# connector_schematic.net
KiCad netlist of a schematic drawn in EAGLE
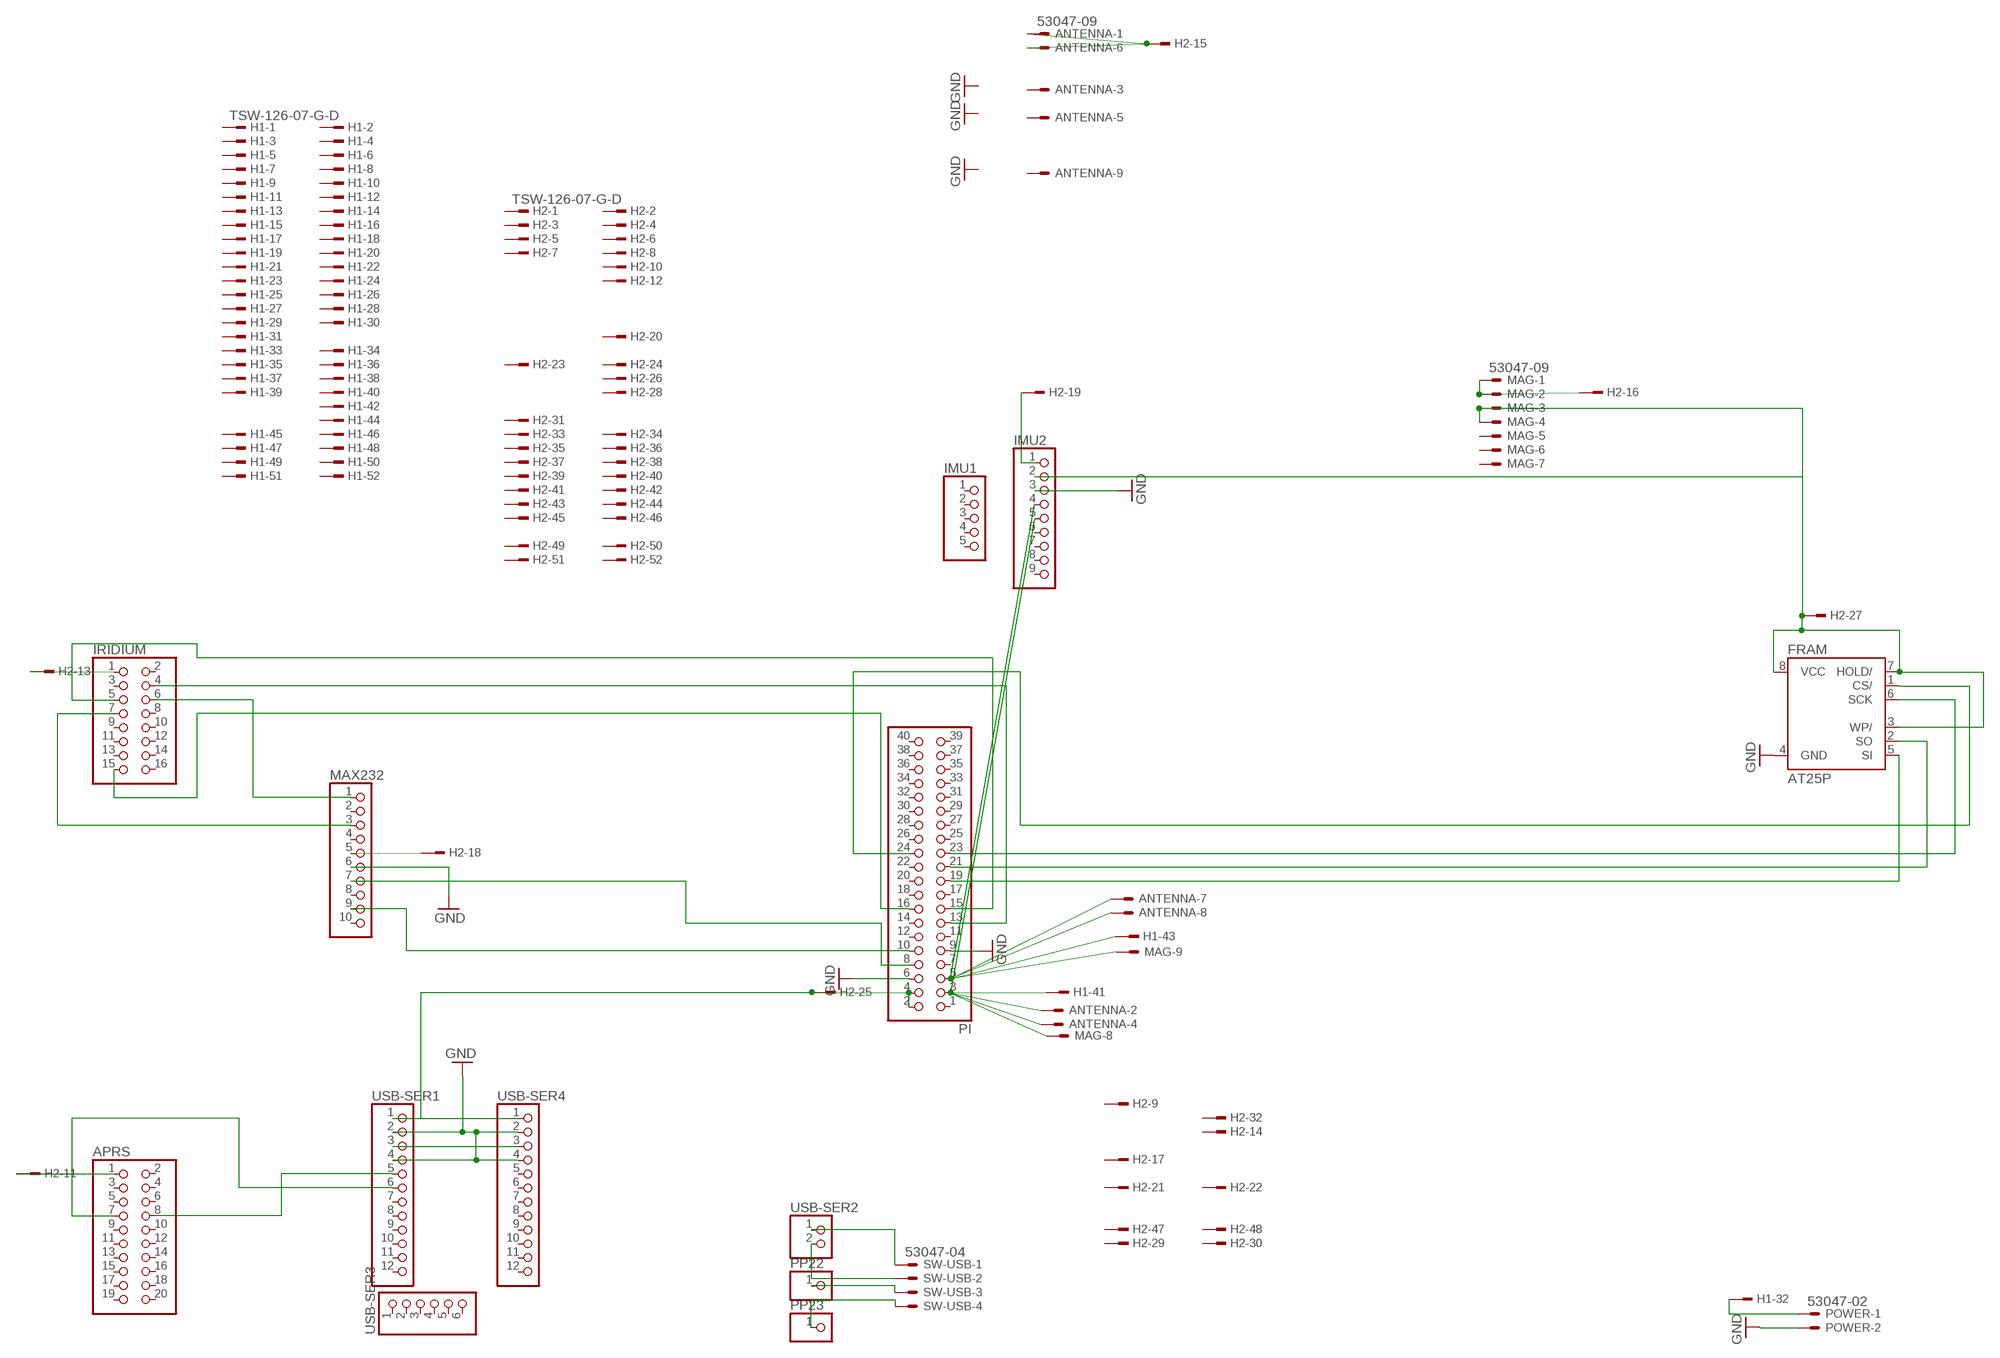
[diagram p0: schematic, sheet 1]

(export (version "E")
  (design (tool "Eeschema 10.0.6"))
  (components
    (comp (ref "ANTENNA")
      (value "53047-09")
      (footprint "eagle-import:53047-09")
      (fields (field (name "MF") "MOLEX") (field (name "MPN") "53047-0910"))
      (libsource (lib "eagle-import") (part "53?-09047"))
    )
    (comp (ref "APRS")
      (value "PINHD-2X10")
      (footprint "eagle-import:2X10")
      (libsource (lib "eagle-import") (part "PINHD-2X10"))
    )
    (comp (ref "FRAM")
      (value "AT25P")
      (footprint "eagle-import:DIL08")
      (fields (field (name "MPN") "CAT25040LI-G"))
      (libsource (lib "eagle-import") (part "AT25P"))
    )
    (comp (ref "H1")
      (value "TSW-126-07-G-D")
      (footprint "eagle-import:TSW-126-XX-G-D")
      (fields (field (name "MF") "Samtec Inc."))
      (libsource (lib "eagle-import") (part "TSW-126--G-D07"))
    )
    (comp (ref "H2")
      (value "TSW-126-07-G-D")
      (footprint "eagle-import:TSW-126-XX-G-D")
      (fields (field (name "MF") "Samtec Inc."))
      (libsource (lib "eagle-import") (part "TSW-126--G-D07"))
    )
    (comp (ref "IMU1")
      (value "PINHD-1X5")
      (footprint "eagle-import:1X05")
      (libsource (lib "eagle-import") (part "PINHD-1X5"))
    )
    (comp (ref "IMU2")
      (value "PINHD-1X9")
      (footprint "eagle-import:1X09")
      (libsource (lib "eagle-import") (part "PINHD-1X9"))
    )
    (comp (ref "IRIDIUM")
      (value "PINHD-2X8")
      (footprint "eagle-import:2X08")
      (libsource (lib "eagle-import") (part "PINHD-2X8"))
    )
    (comp (ref "MAG")
      (value "53047-09")
      (footprint "eagle-import:53047-09")
      (fields (field (name "MF") "MOLEX") (field (name "MPN") "53047-0910"))
      (libsource (lib "eagle-import") (part "53?-09047"))
    )
    (comp (ref "MAX232")
      (value "PINHD-1X10")
      (footprint "eagle-import:1X10")
      (libsource (lib "eagle-import") (part "PINHD-1X10"))
    )
    (comp (ref "PI")
      (value "PINHD-2X20")
      (footprint "eagle-import:2X20")
      (libsource (lib "eagle-import") (part "PINHD-2X20"))
    )
    (comp (ref "POWER")
      (value "53047-02")
      (footprint "eagle-import:53047-02")
      (fields (field (name "MF") "MOLEX") (field (name "MPN") "53047-0210"))
      (libsource (lib "eagle-import") (part "53?-02047"))
    )
    (comp (ref "PP22")
      (value "PINHD-1X1")
      (footprint "eagle-import:1X01")
      (libsource (lib "eagle-import") (part "PINHD-1X1"))
    )
    (comp (ref "PP23")
      (value "PINHD-1X1")
      (footprint "eagle-import:1X01")
      (libsource (lib "eagle-import") (part "PINHD-1X1"))
    )
    (comp (ref "SW-USB")
      (value "53047-04")
      (footprint "eagle-import:53047-04")
      (fields (field (name "MF") "WALDOM/MOLEX") (field (name "MPN") "53047-0410"))
      (libsource (lib "eagle-import") (part "53?-04047"))
    )
    (comp (ref "USB-SER1")
      (value "PINHD-1X12")
      (footprint "eagle-import:1X12")
      (libsource (lib "eagle-import") (part "PINHD-1X12"))
    )
    (comp (ref "USB-SER2")
      (value "PINHD-1X2")
      (footprint "eagle-import:1X02")
      (libsource (lib "eagle-import") (part "PINHD-1X2"))
    )
    (comp (ref "USB-SER3")
      (value "PINHD-1X6")
      (footprint "eagle-import:1X06")
      (libsource (lib "eagle-import") (part "PINHD-1X6"))
    )
    (comp (ref "USB-SER4")
      (value "PINHD-1X12")
      (footprint "eagle-import:1X12")
      (libsource (lib "eagle-import") (part "PINHD-1X12"))
    )
  )
  (nets
    (net (code "1") (name "GND") (class "Default")
      (node (ref "FRAM") (pin "4") (pinfunction "GND_4") (pintype "power_in"))
      (node (ref "IMU2") (pin "3") (pinfunction "3_3") (pintype "passive"))
      (node (ref "MAX232") (pin "6") (pinfunction "6_6") (pintype "passive"))
      (node (ref "PI") (pin "6") (pinfunction "6_6") (pintype "passive"))
      (node (ref "PI") (pin "9") (pinfunction "9_9") (pintype "passive"))
      (node (ref "POWER") (pin "2") (pinfunction "S_2") (pintype "passive"))
      (node (ref "USB-SER1") (pin "2") (pinfunction "2_2") (pintype "passive"))
      (node (ref "USB-SER1") (pin "4") (pinfunction "4_4") (pintype "passive"))
      (node (ref "USB-SER4") (pin "2") (pinfunction "2_2") (pintype "passive"))
      (node (ref "USB-SER4") (pin "4") (pinfunction "4_4") (pintype "passive"))
    )
    (net (code "2") (name "Net-(ANTENNAA-S)") (class "Default")
      (node (ref "ANTENNA") (pin "1") (pinfunction "S_1") (pintype "passive"))
      (node (ref "ANTENNA") (pin "6") (pinfunction "S_6") (pintype "passive"))
      (node (ref "H2") (pin "15") (pinfunction "1_15") (pintype "passive"))
    )
    (net (code "3") (name "Net-(ANTENNAB-S)") (class "Default")
      (node (ref "ANTENNA") (pin "2") (pinfunction "S_2") (pintype "passive"))
      (node (ref "ANTENNA") (pin "4") (pinfunction "S_4") (pintype "passive"))
      (node (ref "H1") (pin "41") (pinfunction "1_41") (pintype "passive"))
      (node (ref "IMU2") (pin "5") (pinfunction "5_5") (pintype "passive"))
      (node (ref "MAG") (pin "8") (pinfunction "S_8") (pintype "passive"))
      (node (ref "PI") (pin "3") (pinfunction "3_3") (pintype "passive"))
    )
    (net (code "4") (name "Net-(ANTENNAG-S)") (class "Default")
      (node (ref "ANTENNA") (pin "7") (pinfunction "S_7") (pintype "passive"))
      (node (ref "ANTENNA") (pin "8") (pinfunction "S_8") (pintype "passive"))
      (node (ref "H1") (pin "43") (pinfunction "1_43") (pintype "passive"))
      (node (ref "IMU2") (pin "4") (pinfunction "4_4") (pintype "passive"))
      (node (ref "MAG") (pin "9") (pinfunction "S_9") (pintype "passive"))
      (node (ref "PI") (pin "5") (pinfunction "5_5") (pintype "passive"))
    )
    (net (code "5") (name "Net-(APRS-Pad7)") (class "Default")
      (node (ref "APRS") (pin "7") (pinfunction "7_7") (pintype "passive"))
      (node (ref "USB-SER1") (pin "6") (pinfunction "6_6") (pintype "passive"))
    )
    (net (code "6") (name "Net-(APRS-Pad8)") (class "Default")
      (node (ref "APRS") (pin "8") (pinfunction "8_8") (pintype "passive"))
      (node (ref "USB-SER1") (pin "5") (pinfunction "5_5") (pintype "passive"))
    )
    (net (code "7") (name "Net-(FRAM-CS{slash})") (class "Default")
      (node (ref "FRAM") (pin "1") (pinfunction "CS/_1") (pintype "input"))
      (node (ref "PI") (pin "24") (pinfunction "24_24") (pintype "passive"))
    )
    (net (code "8") (name "Net-(FRAM-HOLD{slash})") (class "Default")
      (node (ref "FRAM") (pin "3") (pinfunction "WP/_3") (pintype "input"))
      (node (ref "FRAM") (pin "7") (pinfunction "HOLD/_7") (pintype "input"))
      (node (ref "FRAM") (pin "8") (pinfunction "VCC_8") (pintype "power_in"))
      (node (ref "H2") (pin "27") (pinfunction "1_27") (pintype "passive"))
      (node (ref "IMU2") (pin "2") (pinfunction "2_2") (pintype "passive"))
      (node (ref "MAG") (pin "3") (pinfunction "S_3") (pintype "passive"))
      (node (ref "MAG") (pin "4") (pinfunction "S_4") (pintype "passive"))
    )
    (net (code "9") (name "Net-(FRAM-SCK)") (class "Default")
      (node (ref "FRAM") (pin "6") (pinfunction "SCK_6") (pintype "bidirectional"))
      (node (ref "PI") (pin "23") (pinfunction "23_23") (pintype "passive"))
    )
    (net (code "10") (name "Net-(FRAM-SI)") (class "Default")
      (node (ref "FRAM") (pin "5") (pinfunction "SI_5") (pintype "bidirectional"))
      (node (ref "PI") (pin "19") (pinfunction "19_19") (pintype "passive"))
    )
    (net (code "11") (name "Net-(FRAM-SO)") (class "Default")
      (node (ref "FRAM") (pin "2") (pinfunction "SO_2") (pintype "input"))
      (node (ref "PI") (pin "21") (pinfunction "21_21") (pintype "passive"))
    )
    (net (code "12") (name "Net-(H1Z-1)") (class "Default")
      (node (ref "H1") (pin "32") (pinfunction "1_32") (pintype "passive"))
      (node (ref "POWER") (pin "1") (pinfunction "S_1") (pintype "passive"))
    )
    (net (code "13") (name "Net-(H2C-1)") (class "Default")
      (node (ref "APRS") (pin "1") (pinfunction "1_1") (pintype "passive"))
      (node (ref "H2") (pin "11") (pinfunction "1_11") (pintype "passive"))
    )
    (net (code "14") (name "Net-(H2E-1)") (class "Default")
      (node (ref "H2") (pin "13") (pinfunction "1_13") (pintype "passive"))
      (node (ref "IRIDIUM") (pin "1") (pinfunction "1_1") (pintype "passive"))
    )
    (net (code "15") (name "Net-(H2H-1)") (class "Default")
      (node (ref "H2") (pin "16") (pinfunction "1_16") (pintype "passive"))
      (node (ref "MAG") (pin "1") (pinfunction "S_1") (pintype "passive"))
      (node (ref "MAG") (pin "2") (pinfunction "S_2") (pintype "passive"))
    )
    (net (code "16") (name "Net-(H2J-1)") (class "Default")
      (node (ref "H2") (pin "18") (pinfunction "1_18") (pintype "passive"))
      (node (ref "MAX232") (pin "5") (pinfunction "5_5") (pintype "passive"))
    )
    (net (code "17") (name "Net-(H2K-1)") (class "Default")
      (node (ref "H2") (pin "19") (pinfunction "1_19") (pintype "passive"))
      (node (ref "IMU2") (pin "1") (pinfunction "1_1") (pintype "passive"))
    )
    (net (code "18") (name "Net-(H2R-1)") (class "Default")
      (node (ref "H2") (pin "25") (pinfunction "1_25") (pintype "passive"))
      (node (ref "PI") (pin "2") (pinfunction "2_2") (pintype "passive"))
      (node (ref "PI") (pin "4") (pinfunction "4_4") (pintype "passive"))
      (node (ref "USB-SER1") (pin "1") (pinfunction "1_1") (pintype "passive"))
      (node (ref "USB-SER4") (pin "1") (pinfunction "1_1") (pintype "passive"))
    )
    (net (code "19") (name "Net-(IRIDIUM-Pad4)") (class "Default")
      (node (ref "IRIDIUM") (pin "4") (pinfunction "4_4") (pintype "passive"))
      (node (ref "PI") (pin "13") (pinfunction "13_13") (pintype "passive"))
    )
    (net (code "20") (name "Net-(IRIDIUM-Pad5)") (class "Default")
      (node (ref "IRIDIUM") (pin "5") (pinfunction "5_5") (pintype "passive"))
      (node (ref "PI") (pin "15") (pinfunction "15_15") (pintype "passive"))
    )
    (net (code "21") (name "Net-(IRIDIUM-Pad6)") (class "Default")
      (node (ref "IRIDIUM") (pin "6") (pinfunction "6_6") (pintype "passive"))
      (node (ref "MAX232") (pin "1") (pinfunction "1_1") (pintype "passive"))
    )
    (net (code "22") (name "Net-(IRIDIUM-Pad7)") (class "Default")
      (node (ref "IRIDIUM") (pin "7") (pinfunction "7_7") (pintype "passive"))
      (node (ref "MAX232") (pin "3") (pinfunction "3_3") (pintype "passive"))
    )
    (net (code "23") (name "Net-(IRIDIUM-Pad15)") (class "Default")
      (node (ref "IRIDIUM") (pin "15") (pinfunction "15_15") (pintype "passive"))
      (node (ref "PI") (pin "16") (pinfunction "16_16") (pintype "passive"))
    )
    (net (code "24") (name "Net-(MAX232-Pad7)") (class "Default")
      (node (ref "MAX232") (pin "7") (pinfunction "7_7") (pintype "passive"))
      (node (ref "PI") (pin "8") (pinfunction "8_8") (pintype "passive"))
    )
    (net (code "25") (name "Net-(MAX232-Pad9)") (class "Default")
      (node (ref "MAX232") (pin "9") (pinfunction "9_9") (pintype "passive"))
      (node (ref "PI") (pin "10") (pinfunction "10_10") (pintype "passive"))
    )
    (net (code "26") (name "Net-(SW-USBB-S)") (class "Default")
      (node (ref "SW-USB") (pin "2") (pinfunction "S_2") (pintype "passive"))
      (node (ref "USB-SER2") (pin "2") (pinfunction "2_2") (pintype "passive"))
    )
    (net (code "27") (name "Net-(SW-USBC-S)") (class "Default")
      (node (ref "PP22") (pin "1") (pinfunction "1_1") (pintype "passive"))
      (node (ref "SW-USB") (pin "3") (pinfunction "S_3") (pintype "passive"))
    )
    (net (code "28") (name "Net-(SW-USBD-S)") (class "Default")
      (node (ref "PP23") (pin "1") (pinfunction "1_1") (pintype "passive"))
      (node (ref "SW-USB") (pin "4") (pinfunction "S_4") (pintype "passive"))
    )
    (net (code "29") (name "Net-(USB-SER1-Pad3)") (class "Default")
      (node (ref "USB-SER1") (pin "3") (pinfunction "3_3") (pintype "passive"))
      (node (ref "USB-SER4") (pin "3") (pinfunction "3_3") (pintype "passive"))
    )
    (net (code "30") (name "unconnected-(ANTENNAC-S-Pad3)") (class "Default")
      (node (ref "ANTENNA") (pin "3") (pinfunction "S_3") (pintype "passive"))
    )
    (net (code "31") (name "unconnected-(ANTENNAE-S-Pad5)") (class "Default")
      (node (ref "ANTENNA") (pin "5") (pinfunction "S_5") (pintype "passive"))
    )
    (net (code "32") (name "unconnected-(ANTENNAI-S-Pad9)") (class "Default")
      (node (ref "ANTENNA") (pin "9") (pinfunction "S_9") (pintype "passive"))
    )
    (net (code "33") (name "unconnected-(APRS-Pad2)") (class "Default")
      (node (ref "APRS") (pin "2") (pinfunction "2_2") (pintype "passive"))
    )
    (net (code "34") (name "unconnected-(APRS-Pad3)") (class "Default")
      (node (ref "APRS") (pin "3") (pinfunction "3_3") (pintype "passive"))
    )
    (net (code "35") (name "unconnected-(APRS-Pad4)") (class "Default")
      (node (ref "APRS") (pin "4") (pinfunction "4_4") (pintype "passive"))
    )
    (net (code "36") (name "unconnected-(APRS-Pad5)") (class "Default")
      (node (ref "APRS") (pin "5") (pinfunction "5_5") (pintype "passive"))
    )
    (net (code "37") (name "unconnected-(APRS-Pad6)") (class "Default")
      (node (ref "APRS") (pin "6") (pinfunction "6_6") (pintype "passive"))
    )
    (net (code "38") (name "unconnected-(APRS-Pad9)") (class "Default")
      (node (ref "APRS") (pin "9") (pinfunction "9_9") (pintype "passive"))
    )
    (net (code "39") (name "unconnected-(APRS-Pad10)") (class "Default")
      (node (ref "APRS") (pin "10") (pinfunction "10_10") (pintype "passive"))
    )
    (net (code "40") (name "unconnected-(APRS-Pad11)") (class "Default")
      (node (ref "APRS") (pin "11") (pinfunction "11_11") (pintype "passive"))
    )
    (net (code "41") (name "unconnected-(APRS-Pad12)") (class "Default")
      (node (ref "APRS") (pin "12") (pinfunction "12_12") (pintype "passive"))
    )
    (net (code "42") (name "unconnected-(APRS-Pad13)") (class "Default")
      (node (ref "APRS") (pin "13") (pinfunction "13_13") (pintype "passive"))
    )
    (net (code "43") (name "unconnected-(APRS-Pad14)") (class "Default")
      (node (ref "APRS") (pin "14") (pinfunction "14_14") (pintype "passive"))
    )
    (net (code "44") (name "unconnected-(APRS-Pad15)") (class "Default")
      (node (ref "APRS") (pin "15") (pinfunction "15_15") (pintype "passive"))
    )
    (net (code "45") (name "unconnected-(APRS-Pad16)") (class "Default")
      (node (ref "APRS") (pin "16") (pinfunction "16_16") (pintype "passive"))
    )
    (net (code "46") (name "unconnected-(APRS-Pad17)") (class "Default")
      (node (ref "APRS") (pin "17") (pinfunction "17_17") (pintype "passive"))
    )
    (net (code "47") (name "unconnected-(APRS-Pad18)") (class "Default")
      (node (ref "APRS") (pin "18") (pinfunction "18_18") (pintype "passive"))
    )
    (net (code "48") (name "unconnected-(APRS-Pad19)") (class "Default")
      (node (ref "APRS") (pin "19") (pinfunction "19_19") (pintype "passive"))
    )
    (net (code "49") (name "unconnected-(APRS-Pad20)") (class "Default")
      (node (ref "APRS") (pin "20") (pinfunction "20_20") (pintype "passive"))
    )
    (net (code "50") (name "unconnected-(H1-Pad1)") (class "Default")
      (node (ref "H1") (pin "1") (pinfunction "1_1") (pintype "passive"))
    )
    (net (code "51") (name "unconnected-(H1AA-1-Pad33)") (class "Default")
      (node (ref "H1") (pin "33") (pinfunction "1_33") (pintype "passive"))
    )
    (net (code "52") (name "unconnected-(H1AB-1-Pad34)") (class "Default")
      (node (ref "H1") (pin "34") (pinfunction "1_34") (pintype "passive"))
    )
    (net (code "53") (name "unconnected-(H1AC-1-Pad35)") (class "Default")
      (node (ref "H1") (pin "35") (pinfunction "1_35") (pintype "passive"))
    )
    (net (code "54") (name "unconnected-(H1AD-1-Pad36)") (class "Default")
      (node (ref "H1") (pin "36") (pinfunction "1_36") (pintype "passive"))
    )
    (net (code "55") (name "unconnected-(H1AE-1-Pad37)") (class "Default")
      (node (ref "H1") (pin "37") (pinfunction "1_37") (pintype "passive"))
    )
    (net (code "56") (name "unconnected-(H1AF-1-Pad38)") (class "Default")
      (node (ref "H1") (pin "38") (pinfunction "1_38") (pintype "passive"))
    )
    (net (code "57") (name "unconnected-(H1AG-1-Pad39)") (class "Default")
      (node (ref "H1") (pin "39") (pinfunction "1_39") (pintype "passive"))
    )
    (net (code "58") (name "unconnected-(H1AH-1-Pad4)") (class "Default")
      (node (ref "H1") (pin "4") (pinfunction "1_4") (pintype "passive"))
    )
    (net (code "59") (name "unconnected-(H1AI-1-Pad40)") (class "Default")
      (node (ref "H1") (pin "40") (pinfunction "1_40") (pintype "passive"))
    )
    (net (code "60") (name "unconnected-(H1AK-1-Pad42)") (class "Default")
      (node (ref "H1") (pin "42") (pinfunction "1_42") (pintype "passive"))
    )
    (net (code "61") (name "unconnected-(H1AM-1-Pad44)") (class "Default")
      (node (ref "H1") (pin "44") (pinfunction "1_44") (pintype "passive"))
    )
    (net (code "62") (name "unconnected-(H1AN-1-Pad45)") (class "Default")
      (node (ref "H1") (pin "45") (pinfunction "1_45") (pintype "passive"))
    )
    (net (code "63") (name "unconnected-(H1AO-1-Pad46)") (class "Default")
      (node (ref "H1") (pin "46") (pinfunction "1_46") (pintype "passive"))
    )
    (net (code "64") (name "unconnected-(H1AP-1-Pad47)") (class "Default")
      (node (ref "H1") (pin "47") (pinfunction "1_47") (pintype "passive"))
    )
    (net (code "65") (name "unconnected-(H1AQ-1-Pad48)") (class "Default")
      (node (ref "H1") (pin "48") (pinfunction "1_48") (pintype "passive"))
    )
    (net (code "66") (name "unconnected-(H1AR-1-Pad49)") (class "Default")
      (node (ref "H1") (pin "49") (pinfunction "1_49") (pintype "passive"))
    )
    (net (code "67") (name "unconnected-(H1AS-1-Pad5)") (class "Default")
      (node (ref "H1") (pin "5") (pinfunction "1_5") (pintype "passive"))
    )
    (net (code "68") (name "unconnected-(H1AT-1-Pad50)") (class "Default")
      (node (ref "H1") (pin "50") (pinfunction "1_50") (pintype "passive"))
    )
    (net (code "69") (name "unconnected-(H1AU-1-Pad51)") (class "Default")
      (node (ref "H1") (pin "51") (pinfunction "1_51") (pintype "passive"))
    )
    (net (code "70") (name "unconnected-(H1AV-1-Pad52)") (class "Default")
      (node (ref "H1") (pin "52") (pinfunction "1_52") (pintype "passive"))
    )
    (net (code "71") (name "unconnected-(H1AW-1-Pad6)") (class "Default")
      (node (ref "H1") (pin "6") (pinfunction "1_6") (pintype "passive"))
    )
    (net (code "72") (name "unconnected-(H1AX-1-Pad7)") (class "Default")
      (node (ref "H1") (pin "7") (pinfunction "1_7") (pintype "passive"))
    )
    (net (code "73") (name "unconnected-(H1AY-1-Pad8)") (class "Default")
      (node (ref "H1") (pin "8") (pinfunction "1_8") (pintype "passive"))
    )
    (net (code "74") (name "unconnected-(H1AZ-1-Pad9)") (class "Default")
      (node (ref "H1") (pin "9") (pinfunction "1_9") (pintype "passive"))
    )
    (net (code "75") (name "unconnected-(H1B-1-Pad10)") (class "Default")
      (node (ref "H1") (pin "10") (pinfunction "1_10") (pintype "passive"))
    )
    (net (code "76") (name "unconnected-(H1C-1-Pad11)") (class "Default")
      (node (ref "H1") (pin "11") (pinfunction "1_11") (pintype "passive"))
    )
    (net (code "77") (name "unconnected-(H1D-1-Pad12)") (class "Default")
      (node (ref "H1") (pin "12") (pinfunction "1_12") (pintype "passive"))
    )
    (net (code "78") (name "unconnected-(H1E-1-Pad13)") (class "Default")
      (node (ref "H1") (pin "13") (pinfunction "1_13") (pintype "passive"))
    )
    (net (code "79") (name "unconnected-(H1F-1-Pad14)") (class "Default")
      (node (ref "H1") (pin "14") (pinfunction "1_14") (pintype "passive"))
    )
    (net (code "80") (name "unconnected-(H1G-1-Pad15)") (class "Default")
      (node (ref "H1") (pin "15") (pinfunction "1_15") (pintype "passive"))
    )
    (net (code "81") (name "unconnected-(H1H-1-Pad16)") (class "Default")
      (node (ref "H1") (pin "16") (pinfunction "1_16") (pintype "passive"))
    )
    (net (code "82") (name "unconnected-(H1I-1-Pad17)") (class "Default")
      (node (ref "H1") (pin "17") (pinfunction "1_17") (pintype "passive"))
    )
    (net (code "83") (name "unconnected-(H1J-1-Pad18)") (class "Default")
      (node (ref "H1") (pin "18") (pinfunction "1_18") (pintype "passive"))
    )
    (net (code "84") (name "unconnected-(H1K-1-Pad19)") (class "Default")
      (node (ref "H1") (pin "19") (pinfunction "1_19") (pintype "passive"))
    )
    (net (code "85") (name "unconnected-(H1L-1-Pad2)") (class "Default")
      (node (ref "H1") (pin "2") (pinfunction "1_2") (pintype "passive"))
    )
    (net (code "86") (name "unconnected-(H1M-1-Pad20)") (class "Default")
      (node (ref "H1") (pin "20") (pinfunction "1_20") (pintype "passive"))
    )
    (net (code "87") (name "unconnected-(H1N-1-Pad21)") (class "Default")
      (node (ref "H1") (pin "21") (pinfunction "1_21") (pintype "passive"))
    )
    (net (code "88") (name "unconnected-(H1O-1-Pad22)") (class "Default")
      (node (ref "H1") (pin "22") (pinfunction "1_22") (pintype "passive"))
    )
    (net (code "89") (name "unconnected-(H1P-1-Pad23)") (class "Default")
      (node (ref "H1") (pin "23") (pinfunction "1_23") (pintype "passive"))
    )
    (net (code "90") (name "unconnected-(H1Q-1-Pad24)") (class "Default")
      (node (ref "H1") (pin "24") (pinfunction "1_24") (pintype "passive"))
    )
    (net (code "91") (name "unconnected-(H1R-1-Pad25)") (class "Default")
      (node (ref "H1") (pin "25") (pinfunction "1_25") (pintype "passive"))
    )
    (net (code "92") (name "unconnected-(H1S-1-Pad26)") (class "Default")
      (node (ref "H1") (pin "26") (pinfunction "1_26") (pintype "passive"))
    )
    (net (code "93") (name "unconnected-(H1T-1-Pad27)") (class "Default")
      (node (ref "H1") (pin "27") (pinfunction "1_27") (pintype "passive"))
    )
    (net (code "94") (name "unconnected-(H1U-1-Pad28)") (class "Default")
      (node (ref "H1") (pin "28") (pinfunction "1_28") (pintype "passive"))
    )
    (net (code "95") (name "unconnected-(H1V-1-Pad29)") (class "Default")
      (node (ref "H1") (pin "29") (pinfunction "1_29") (pintype "passive"))
    )
    (net (code "96") (name "unconnected-(H1W-1-Pad3)") (class "Default")
      (node (ref "H1") (pin "3") (pinfunction "1_3") (pintype "passive"))
    )
    (net (code "97") (name "unconnected-(H1X-1-Pad30)") (class "Default")
      (node (ref "H1") (pin "30") (pinfunction "1_30") (pintype "passive"))
    )
    (net (code "98") (name "unconnected-(H1Y-1-Pad31)") (class "Default")
      (node (ref "H1") (pin "31") (pinfunction "1_31") (pintype "passive"))
    )
    (net (code "99") (name "unconnected-(H2-Pad1)") (class "Default")
      (node (ref "H2") (pin "1") (pinfunction "1_1") (pintype "passive"))
    )
    (net (code "100") (name "unconnected-(H2AA-1-Pad33)") (class "Default")
      (node (ref "H2") (pin "33") (pinfunction "1_33") (pintype "passive"))
    )
    (net (code "101") (name "unconnected-(H2AB-1-Pad34)") (class "Default")
      (node (ref "H2") (pin "34") (pinfunction "1_34") (pintype "passive"))
    )
    (net (code "102") (name "unconnected-(H2AC-1-Pad35)") (class "Default")
      (node (ref "H2") (pin "35") (pinfunction "1_35") (pintype "passive"))
    )
    (net (code "103") (name "unconnected-(H2AD-1-Pad36)") (class "Default")
      (node (ref "H2") (pin "36") (pinfunction "1_36") (pintype "passive"))
    )
    (net (code "104") (name "unconnected-(H2AE-1-Pad37)") (class "Default")
      (node (ref "H2") (pin "37") (pinfunction "1_37") (pintype "passive"))
    )
    (net (code "105") (name "unconnected-(H2AF-1-Pad38)") (class "Default")
      (node (ref "H2") (pin "38") (pinfunction "1_38") (pintype "passive"))
    )
    (net (code "106") (name "unconnected-(H2AG-1-Pad39)") (class "Default")
      (node (ref "H2") (pin "39") (pinfunction "1_39") (pintype "passive"))
    )
    (net (code "107") (name "unconnected-(H2AH-1-Pad4)") (class "Default")
      (node (ref "H2") (pin "4") (pinfunction "1_4") (pintype "passive"))
    )
    (net (code "108") (name "unconnected-(H2AI-1-Pad40)") (class "Default")
      (node (ref "H2") (pin "40") (pinfunction "1_40") (pintype "passive"))
    )
    (net (code "109") (name "unconnected-(H2AJ-1-Pad41)") (class "Default")
      (node (ref "H2") (pin "41") (pinfunction "1_41") (pintype "passive"))
    )
    (net (code "110") (name "unconnected-(H2AK-1-Pad42)") (class "Default")
      (node (ref "H2") (pin "42") (pinfunction "1_42") (pintype "passive"))
    )
    (net (code "111") (name "unconnected-(H2AL-1-Pad43)") (class "Default")
      (node (ref "H2") (pin "43") (pinfunction "1_43") (pintype "passive"))
    )
    (net (code "112") (name "unconnected-(H2AM-1-Pad44)") (class "Default")
      (node (ref "H2") (pin "44") (pinfunction "1_44") (pintype "passive"))
    )
    (net (code "113") (name "unconnected-(H2AN-1-Pad45)") (class "Default")
      (node (ref "H2") (pin "45") (pinfunction "1_45") (pintype "passive"))
    )
    (net (code "114") (name "unconnected-(H2AO-1-Pad46)") (class "Default")
      (node (ref "H2") (pin "46") (pinfunction "1_46") (pintype "passive"))
    )
    (net (code "115") (name "unconnected-(H2AP-1-Pad47)") (class "Default")
      (node (ref "H2") (pin "47") (pinfunction "1_47") (pintype "passive"))
    )
    (net (code "116") (name "unconnected-(H2AQ-1-Pad48)") (class "Default")
      (node (ref "H2") (pin "48") (pinfunction "1_48") (pintype "passive"))
    )
    (net (code "117") (name "unconnected-(H2AR-1-Pad49)") (class "Default")
      (node (ref "H2") (pin "49") (pinfunction "1_49") (pintype "passive"))
    )
    (net (code "118") (name "unconnected-(H2AS-1-Pad5)") (class "Default")
      (node (ref "H2") (pin "5") (pinfunction "1_5") (pintype "passive"))
    )
    (net (code "119") (name "unconnected-(H2AT-1-Pad50)") (class "Default")
      (node (ref "H2") (pin "50") (pinfunction "1_50") (pintype "passive"))
    )
    (net (code "120") (name "unconnected-(H2AU-1-Pad51)") (class "Default")
      (node (ref "H2") (pin "51") (pinfunction "1_51") (pintype "passive"))
    )
    (net (code "121") (name "unconnected-(H2AV-1-Pad52)") (class "Default")
      (node (ref "H2") (pin "52") (pinfunction "1_52") (pintype "passive"))
    )
    (net (code "122") (name "unconnected-(H2AW-1-Pad6)") (class "Default")
      (node (ref "H2") (pin "6") (pinfunction "1_6") (pintype "passive"))
    )
    (net (code "123") (name "unconnected-(H2AX-1-Pad7)") (class "Default")
      (node (ref "H2") (pin "7") (pinfunction "1_7") (pintype "passive"))
    )
    (net (code "124") (name "unconnected-(H2AY-1-Pad8)") (class "Default")
      (node (ref "H2") (pin "8") (pinfunction "1_8") (pintype "passive"))
    )
    (net (code "125") (name "unconnected-(H2AZ-1-Pad9)") (class "Default")
      (node (ref "H2") (pin "9") (pinfunction "1_9") (pintype "passive"))
    )
    (net (code "126") (name "unconnected-(H2B-1-Pad10)") (class "Default")
      (node (ref "H2") (pin "10") (pinfunction "1_10") (pintype "passive"))
    )
    (net (code "127") (name "unconnected-(H2D-1-Pad12)") (class "Default")
      (node (ref "H2") (pin "12") (pinfunction "1_12") (pintype "passive"))
    )
    (net (code "128") (name "unconnected-(H2F-1-Pad14)") (class "Default")
      (node (ref "H2") (pin "14") (pinfunction "1_14") (pintype "passive"))
    )
    (net (code "129") (name "unconnected-(H2I-1-Pad17)") (class "Default")
      (node (ref "H2") (pin "17") (pinfunction "1_17") (pintype "passive"))
    )
    (net (code "130") (name "unconnected-(H2L-1-Pad2)") (class "Default")
      (node (ref "H2") (pin "2") (pinfunction "1_2") (pintype "passive"))
    )
    (net (code "131") (name "unconnected-(H2M-1-Pad20)") (class "Default")
      (node (ref "H2") (pin "20") (pinfunction "1_20") (pintype "passive"))
    )
    (net (code "132") (name "unconnected-(H2N-1-Pad21)") (class "Default")
      (node (ref "H2") (pin "21") (pinfunction "1_21") (pintype "passive"))
    )
    (net (code "133") (name "unconnected-(H2O-1-Pad22)") (class "Default")
      (node (ref "H2") (pin "22") (pinfunction "1_22") (pintype "passive"))
    )
    (net (code "134") (name "unconnected-(H2P-1-Pad23)") (class "Default")
      (node (ref "H2") (pin "23") (pinfunction "1_23") (pintype "passive"))
    )
    (net (code "135") (name "unconnected-(H2Q-1-Pad24)") (class "Default")
      (node (ref "H2") (pin "24") (pinfunction "1_24") (pintype "passive"))
    )
    (net (code "136") (name "unconnected-(H2S-1-Pad26)") (class "Default")
      (node (ref "H2") (pin "26") (pinfunction "1_26") (pintype "passive"))
    )
    (net (code "137") (name "unconnected-(H2U-1-Pad28)") (class "Default")
      (node (ref "H2") (pin "28") (pinfunction "1_28") (pintype "passive"))
    )
    (net (code "138") (name "unconnected-(H2V-1-Pad29)") (class "Default")
      (node (ref "H2") (pin "29") (pinfunction "1_29") (pintype "passive"))
    )
    (net (code "139") (name "unconnected-(H2W-1-Pad3)") (class "Default")
      (node (ref "H2") (pin "3") (pinfunction "1_3") (pintype "passive"))
    )
    (net (code "140") (name "unconnected-(H2X-1-Pad30)") (class "Default")
      (node (ref "H2") (pin "30") (pinfunction "1_30") (pintype "passive"))
    )
    (net (code "141") (name "unconnected-(H2Y-1-Pad31)") (class "Default")
      (node (ref "H2") (pin "31") (pinfunction "1_31") (pintype "passive"))
    )
    (net (code "142") (name "unconnected-(H2Z-1-Pad32)") (class "Default")
      (node (ref "H2") (pin "32") (pinfunction "1_32") (pintype "passive"))
    )
    (net (code "143") (name "unconnected-(IMU1-Pad1)") (class "Default")
      (node (ref "IMU1") (pin "1") (pinfunction "1_1") (pintype "passive"))
    )
    (net (code "144") (name "unconnected-(IMU1-Pad2)") (class "Default")
      (node (ref "IMU1") (pin "2") (pinfunction "2_2") (pintype "passive"))
    )
    (net (code "145") (name "unconnected-(IMU1-Pad3)") (class "Default")
      (node (ref "IMU1") (pin "3") (pinfunction "3_3") (pintype "passive"))
    )
    (net (code "146") (name "unconnected-(IMU1-Pad4)") (class "Default")
      (node (ref "IMU1") (pin "4") (pinfunction "4_4") (pintype "passive"))
    )
    (net (code "147") (name "unconnected-(IMU1-Pad5)") (class "Default")
      (node (ref "IMU1") (pin "5") (pinfunction "5_5") (pintype "passive"))
    )
    (net (code "148") (name "unconnected-(IMU2-Pad6)") (class "Default")
      (node (ref "IMU2") (pin "6") (pinfunction "6_6") (pintype "passive"))
    )
    (net (code "149") (name "unconnected-(IMU2-Pad7)") (class "Default")
      (node (ref "IMU2") (pin "7") (pinfunction "7_7") (pintype "passive"))
    )
    (net (code "150") (name "unconnected-(IMU2-Pad8)") (class "Default")
      (node (ref "IMU2") (pin "8") (pinfunction "8_8") (pintype "passive"))
    )
    (net (code "151") (name "unconnected-(IMU2-Pad9)") (class "Default")
      (node (ref "IMU2") (pin "9") (pinfunction "9_9") (pintype "passive"))
    )
    (net (code "152") (name "unconnected-(IRIDIUM-Pad2)") (class "Default")
      (node (ref "IRIDIUM") (pin "2") (pinfunction "2_2") (pintype "passive"))
    )
    (net (code "153") (name "unconnected-(IRIDIUM-Pad3)") (class "Default")
      (node (ref "IRIDIUM") (pin "3") (pinfunction "3_3") (pintype "passive"))
    )
    (net (code "154") (name "unconnected-(IRIDIUM-Pad8)") (class "Default")
      (node (ref "IRIDIUM") (pin "8") (pinfunction "8_8") (pintype "passive"))
    )
    (net (code "155") (name "unconnected-(IRIDIUM-Pad9)") (class "Default")
      (node (ref "IRIDIUM") (pin "9") (pinfunction "9_9") (pintype "passive"))
    )
    (net (code "156") (name "unconnected-(IRIDIUM-Pad10)") (class "Default")
      (node (ref "IRIDIUM") (pin "10") (pinfunction "10_10") (pintype "passive"))
    )
    (net (code "157") (name "unconnected-(IRIDIUM-Pad11)") (class "Default")
      (node (ref "IRIDIUM") (pin "11") (pinfunction "11_11") (pintype "passive"))
    )
    (net (code "158") (name "unconnected-(IRIDIUM-Pad12)") (class "Default")
      (node (ref "IRIDIUM") (pin "12") (pinfunction "12_12") (pintype "passive"))
    )
    (net (code "159") (name "unconnected-(IRIDIUM-Pad13)") (class "Default")
      (node (ref "IRIDIUM") (pin "13") (pinfunction "13_13") (pintype "passive"))
    )
    (net (code "160") (name "unconnected-(IRIDIUM-Pad14)") (class "Default")
      (node (ref "IRIDIUM") (pin "14") (pinfunction "14_14") (pintype "passive"))
    )
    (net (code "161") (name "unconnected-(IRIDIUM-Pad16)") (class "Default")
      (node (ref "IRIDIUM") (pin "16") (pinfunction "16_16") (pintype "passive"))
    )
    (net (code "162") (name "unconnected-(MAGE-S-Pad5)") (class "Default")
      (node (ref "MAG") (pin "5") (pinfunction "S_5") (pintype "passive"))
    )
    (net (code "163") (name "unconnected-(MAGF-S-Pad6)") (class "Default")
      (node (ref "MAG") (pin "6") (pinfunction "S_6") (pintype "passive"))
    )
    (net (code "164") (name "unconnected-(MAGG-S-Pad7)") (class "Default")
      (node (ref "MAG") (pin "7") (pinfunction "S_7") (pintype "passive"))
    )
    (net (code "165") (name "unconnected-(MAX232-Pad2)") (class "Default")
      (node (ref "MAX232") (pin "2") (pinfunction "2_2") (pintype "passive"))
    )
    (net (code "166") (name "unconnected-(MAX232-Pad4)") (class "Default")
      (node (ref "MAX232") (pin "4") (pinfunction "4_4") (pintype "passive"))
    )
    (net (code "167") (name "unconnected-(MAX232-Pad8)") (class "Default")
      (node (ref "MAX232") (pin "8") (pinfunction "8_8") (pintype "passive"))
    )
    (net (code "168") (name "unconnected-(MAX232-Pad10)") (class "Default")
      (node (ref "MAX232") (pin "10") (pinfunction "10_10") (pintype "passive"))
    )
    (net (code "169") (name "unconnected-(PI-Pad1)") (class "Default")
      (node (ref "PI") (pin "1") (pinfunction "1_1") (pintype "passive"))
    )
    (net (code "170") (name "unconnected-(PI-Pad7)") (class "Default")
      (node (ref "PI") (pin "7") (pinfunction "7_7") (pintype "passive"))
    )
    (net (code "171") (name "unconnected-(PI-Pad11)") (class "Default")
      (node (ref "PI") (pin "11") (pinfunction "11_11") (pintype "passive"))
    )
    (net (code "172") (name "unconnected-(PI-Pad12)") (class "Default")
      (node (ref "PI") (pin "12") (pinfunction "12_12") (pintype "passive"))
    )
    (net (code "173") (name "unconnected-(PI-Pad14)") (class "Default")
      (node (ref "PI") (pin "14") (pinfunction "14_14") (pintype "passive"))
    )
    (net (code "174") (name "unconnected-(PI-Pad17)") (class "Default")
      (node (ref "PI") (pin "17") (pinfunction "17_17") (pintype "passive"))
    )
    (net (code "175") (name "unconnected-(PI-Pad18)") (class "Default")
      (node (ref "PI") (pin "18") (pinfunction "18_18") (pintype "passive"))
    )
    (net (code "176") (name "unconnected-(PI-Pad20)") (class "Default")
      (node (ref "PI") (pin "20") (pinfunction "20_20") (pintype "passive"))
    )
    (net (code "177") (name "unconnected-(PI-Pad22)") (class "Default")
      (node (ref "PI") (pin "22") (pinfunction "22_22") (pintype "passive"))
    )
    (net (code "178") (name "unconnected-(PI-Pad25)") (class "Default")
      (node (ref "PI") (pin "25") (pinfunction "25_25") (pintype "passive"))
    )
    (net (code "179") (name "unconnected-(PI-Pad26)") (class "Default")
      (node (ref "PI") (pin "26") (pinfunction "26_26") (pintype "passive"))
    )
    (net (code "180") (name "unconnected-(PI-Pad27)") (class "Default")
      (node (ref "PI") (pin "27") (pinfunction "27_27") (pintype "passive"))
    )
    (net (code "181") (name "unconnected-(PI-Pad28)") (class "Default")
      (node (ref "PI") (pin "28") (pinfunction "28_28") (pintype "passive"))
    )
    (net (code "182") (name "unconnected-(PI-Pad29)") (class "Default")
      (node (ref "PI") (pin "29") (pinfunction "29_29") (pintype "passive"))
    )
    (net (code "183") (name "unconnected-(PI-Pad30)") (class "Default")
      (node (ref "PI") (pin "30") (pinfunction "30_30") (pintype "passive"))
    )
    (net (code "184") (name "unconnected-(PI-Pad31)") (class "Default")
      (node (ref "PI") (pin "31") (pinfunction "31_31") (pintype "passive"))
    )
    (net (code "185") (name "unconnected-(PI-Pad32)") (class "Default")
      (node (ref "PI") (pin "32") (pinfunction "32_32") (pintype "passive"))
    )
    (net (code "186") (name "unconnected-(PI-Pad33)") (class "Default")
      (node (ref "PI") (pin "33") (pinfunction "33_33") (pintype "passive"))
    )
    (net (code "187") (name "unconnected-(PI-Pad34)") (class "Default")
      (node (ref "PI") (pin "34") (pinfunction "34_34") (pintype "passive"))
    )
    (net (code "188") (name "unconnected-(PI-Pad35)") (class "Default")
      (node (ref "PI") (pin "35") (pinfunction "35_35") (pintype "passive"))
    )
    (net (code "189") (name "unconnected-(PI-Pad36)") (class "Default")
      (node (ref "PI") (pin "36") (pinfunction "36_36") (pintype "passive"))
    )
    (net (code "190") (name "unconnected-(PI-Pad37)") (class "Default")
      (node (ref "PI") (pin "37") (pinfunction "37_37") (pintype "passive"))
    )
    (net (code "191") (name "unconnected-(PI-Pad38)") (class "Default")
      (node (ref "PI") (pin "38") (pinfunction "38_38") (pintype "passive"))
    )
    (net (code "192") (name "unconnected-(PI-Pad39)") (class "Default")
      (node (ref "PI") (pin "39") (pinfunction "39_39") (pintype "passive"))
    )
    (net (code "193") (name "unconnected-(PI-Pad40)") (class "Default")
      (node (ref "PI") (pin "40") (pinfunction "40_40") (pintype "passive"))
    )
    (net (code "194") (name "unconnected-(SW-USBA-S-Pad1)") (class "Default")
      (node (ref "SW-USB") (pin "1") (pinfunction "S_1") (pintype "passive"))
    )
    (net (code "195") (name "unconnected-(USB-SER1-Pad7)") (class "Default")
      (node (ref "USB-SER1") (pin "7") (pinfunction "7_7") (pintype "passive"))
    )
    (net (code "196") (name "unconnected-(USB-SER1-Pad8)") (class "Default")
      (node (ref "USB-SER1") (pin "8") (pinfunction "8_8") (pintype "passive"))
    )
    (net (code "197") (name "unconnected-(USB-SER1-Pad9)") (class "Default")
      (node (ref "USB-SER1") (pin "9") (pinfunction "9_9") (pintype "passive"))
    )
    (net (code "198") (name "unconnected-(USB-SER1-Pad10)") (class "Default")
      (node (ref "USB-SER1") (pin "10") (pinfunction "10_10") (pintype "passive"))
    )
    (net (code "199") (name "unconnected-(USB-SER1-Pad11)") (class "Default")
      (node (ref "USB-SER1") (pin "11") (pinfunction "11_11") (pintype "passive"))
    )
    (net (code "200") (name "unconnected-(USB-SER1-Pad12)") (class "Default")
      (node (ref "USB-SER1") (pin "12") (pinfunction "12_12") (pintype "passive"))
    )
    (net (code "201") (name "unconnected-(USB-SER2-Pad1)") (class "Default")
      (node (ref "USB-SER2") (pin "1") (pinfunction "1_1") (pintype "passive"))
    )
    (net (code "202") (name "unconnected-(USB-SER3-Pad1)") (class "Default")
      (node (ref "USB-SER3") (pin "1") (pinfunction "1_1") (pintype "passive"))
    )
    (net (code "203") (name "unconnected-(USB-SER3-Pad2)") (class "Default")
      (node (ref "USB-SER3") (pin "2") (pinfunction "2_2") (pintype "passive"))
    )
    (net (code "204") (name "unconnected-(USB-SER3-Pad3)") (class "Default")
      (node (ref "USB-SER3") (pin "3") (pinfunction "3_3") (pintype "passive"))
    )
    (net (code "205") (name "unconnected-(USB-SER3-Pad4)") (class "Default")
      (node (ref "USB-SER3") (pin "4") (pinfunction "4_4") (pintype "passive"))
    )
    (net (code "206") (name "unconnected-(USB-SER3-Pad5)") (class "Default")
      (node (ref "USB-SER3") (pin "5") (pinfunction "5_5") (pintype "passive"))
    )
    (net (code "207") (name "unconnected-(USB-SER3-Pad6)") (class "Default")
      (node (ref "USB-SER3") (pin "6") (pinfunction "6_6") (pintype "passive"))
    )
    (net (code "208") (name "unconnected-(USB-SER4-Pad5)") (class "Default")
      (node (ref "USB-SER4") (pin "5") (pinfunction "5_5") (pintype "passive"))
    )
    (net (code "209") (name "unconnected-(USB-SER4-Pad6)") (class "Default")
      (node (ref "USB-SER4") (pin "6") (pinfunction "6_6") (pintype "passive"))
    )
    (net (code "210") (name "unconnected-(USB-SER4-Pad7)") (class "Default")
      (node (ref "USB-SER4") (pin "7") (pinfunction "7_7") (pintype "passive"))
    )
    (net (code "211") (name "unconnected-(USB-SER4-Pad8)") (class "Default")
      (node (ref "USB-SER4") (pin "8") (pinfunction "8_8") (pintype "passive"))
    )
    (net (code "212") (name "unconnected-(USB-SER4-Pad9)") (class "Default")
      (node (ref "USB-SER4") (pin "9") (pinfunction "9_9") (pintype "passive"))
    )
    (net (code "213") (name "unconnected-(USB-SER4-Pad10)") (class "Default")
      (node (ref "USB-SER4") (pin "10") (pinfunction "10_10") (pintype "passive"))
    )
    (net (code "214") (name "unconnected-(USB-SER4-Pad11)") (class "Default")
      (node (ref "USB-SER4") (pin "11") (pinfunction "11_11") (pintype "passive"))
    )
    (net (code "215") (name "unconnected-(USB-SER4-Pad12)") (class "Default")
      (node (ref "USB-SER4") (pin "12") (pinfunction "12_12") (pintype "passive"))
    )
  )
)
